# Solenoid_System.net
KiCad netlist of a schematic drawn in EAGLE
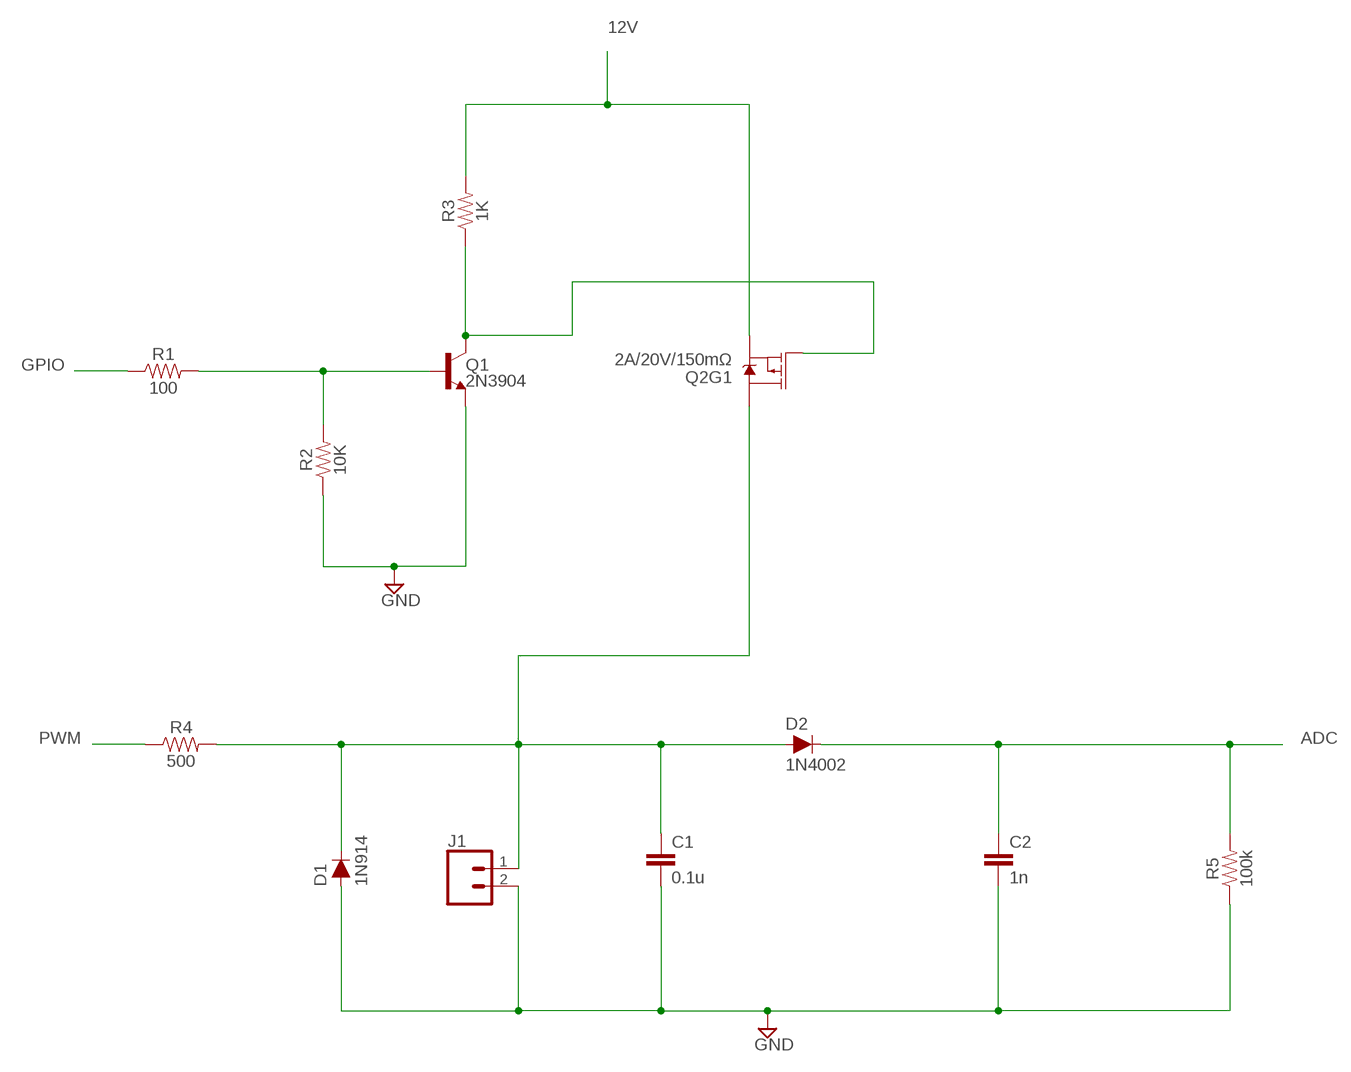
[diagram p0: schematic, sheet 1]

(export (version "E")
  (design (tool "Eeschema 10.0.6"))
  (components
    (comp (ref "C1")
      (value "0.1u")
      (footprint "eagle-import:0603")
      (libsource (lib "eagle-import") (part "10NF-0603-50V-10%"))
    )
    (comp (ref "C2")
      (value "1n")
      (footprint "eagle-import:0603")
      (libsource (lib "eagle-import") (part "10NF-0603-50V-10%"))
    )
    (comp (ref "D1")
      (value "1N914")
      (footprint "eagle-import:SOD-323")
      (libsource (lib "eagle-import") (part "DIODE-BAS16J"))
    )
    (comp (ref "D2")
      (value "1N4002")
      (footprint "eagle-import:SOD-323")
      (libsource (lib "eagle-import") (part "DIODE-BAS16J"))
    )
    (comp (ref "J1")
      (value "CONN_02-JST-2MM-SMT")
      (footprint "eagle-import:JST-2-SMD")
      (libsource (lib "eagle-import") (part "CONN_02-JST-2MM-SMT"))
    )
    (comp (ref "Q1")
      (value "2N3904")
      (footprint "eagle-import:SOT23-3")
      (libsource (lib "eagle-import") (part "TRANS_NPN-MMBT2222AL"))
    )
    (comp (ref "Q2")
      (value "2A/20V/150mΩ")
      (footprint "eagle-import:SOT26")
      (libsource (lib "eagle-import") (part "MOSFET_PCH_DUAL-DMP2240UDM"))
    )
    (comp (ref "R1")
      (value "100")
      (footprint "eagle-import:0603")
      (libsource (lib "eagle-import") (part "10MOHM-0603-1/10W-5%"))
    )
    (comp (ref "R2")
      (value "10K")
      (footprint "eagle-import:0603")
      (libsource (lib "eagle-import") (part "10MOHM-0603-1/10W-5%"))
    )
    (comp (ref "R3")
      (value "1K")
      (footprint "eagle-import:0603")
      (libsource (lib "eagle-import") (part "10MOHM-0603-1/10W-5%"))
    )
    (comp (ref "R4")
      (value "500")
      (footprint "eagle-import:0603")
      (libsource (lib "eagle-import") (part "10MOHM-0603-1/10W-5%"))
    )
    (comp (ref "R5")
      (value "100k")
      (footprint "eagle-import:0603")
      (libsource (lib "eagle-import") (part "10MOHM-0603-1/10W-5%"))
    )
  )
  (nets
    (net (code "1") (name "/12V") (class "Default")
      (node (ref "Q2") (pin "S1") (pinfunction "S_S1") (pintype "bidirectional"))
      (node (ref "R3") (pin "2") (pinfunction "2_2") (pintype "passive"))
    )
    (net (code "2") (name "/ADC") (class "Default")
      (node (ref "C2") (pin "1") (pinfunction "1_1") (pintype "passive"))
      (node (ref "D2") (pin "C") (pinfunction "C_C") (pintype "passive"))
      (node (ref "R5") (pin "2") (pinfunction "2_2") (pintype "passive"))
    )
    (net (code "3") (name "/GPIO") (class "Default")
      (node (ref "R1") (pin "1") (pinfunction "1_1") (pintype "passive"))
    )
    (net (code "4") (name "/PWM") (class "Default")
      (node (ref "R4") (pin "1") (pinfunction "1_1") (pintype "passive"))
    )
    (net (code "5") (name "GND") (class "Default")
      (node (ref "C1") (pin "2") (pinfunction "2_2") (pintype "passive"))
      (node (ref "C2") (pin "2") (pinfunction "2_2") (pintype "passive"))
      (node (ref "D1") (pin "A") (pinfunction "A_A") (pintype "passive"))
      (node (ref "J1") (pin "2") (pinfunction "1_2") (pintype "passive"))
      (node (ref "Q1") (pin "2") (pinfunction "E_2") (pintype "passive"))
      (node (ref "R2") (pin "1") (pinfunction "1_1") (pintype "passive"))
      (node (ref "R5") (pin "1") (pinfunction "1_1") (pintype "passive"))
    )
    (net (code "6") (name "Net-(J1-2)") (class "Default")
      (node (ref "C1") (pin "1") (pinfunction "1_1") (pintype "passive"))
      (node (ref "D1") (pin "C") (pinfunction "C_C") (pintype "passive"))
      (node (ref "D2") (pin "A") (pinfunction "A_A") (pintype "passive"))
      (node (ref "J1") (pin "1") (pinfunction "2_1") (pintype "passive"))
      (node (ref "Q2") (pin "D1") (pinfunction "D_D1") (pintype "bidirectional"))
      (node (ref "R4") (pin "2") (pinfunction "2_2") (pintype "passive"))
    )
    (net (code "7") (name "Net-(Q1-B)") (class "Default")
      (node (ref "Q1") (pin "1") (pinfunction "B_1") (pintype "passive"))
      (node (ref "R1") (pin "2") (pinfunction "2_2") (pintype "passive"))
      (node (ref "R2") (pin "2") (pinfunction "2_2") (pintype "passive"))
    )
    (net (code "8") (name "Net-(Q1-C)") (class "Default")
      (node (ref "Q1") (pin "3") (pinfunction "C_3") (pintype "passive"))
      (node (ref "Q2") (pin "G1") (pinfunction "G_G1") (pintype "bidirectional"))
      (node (ref "R3") (pin "1") (pinfunction "1_1") (pintype "passive"))
    )
  )
)
